# RBPZ_Dynamixel_TI.net
KiCad netlist of a schematic drawn in EAGLE
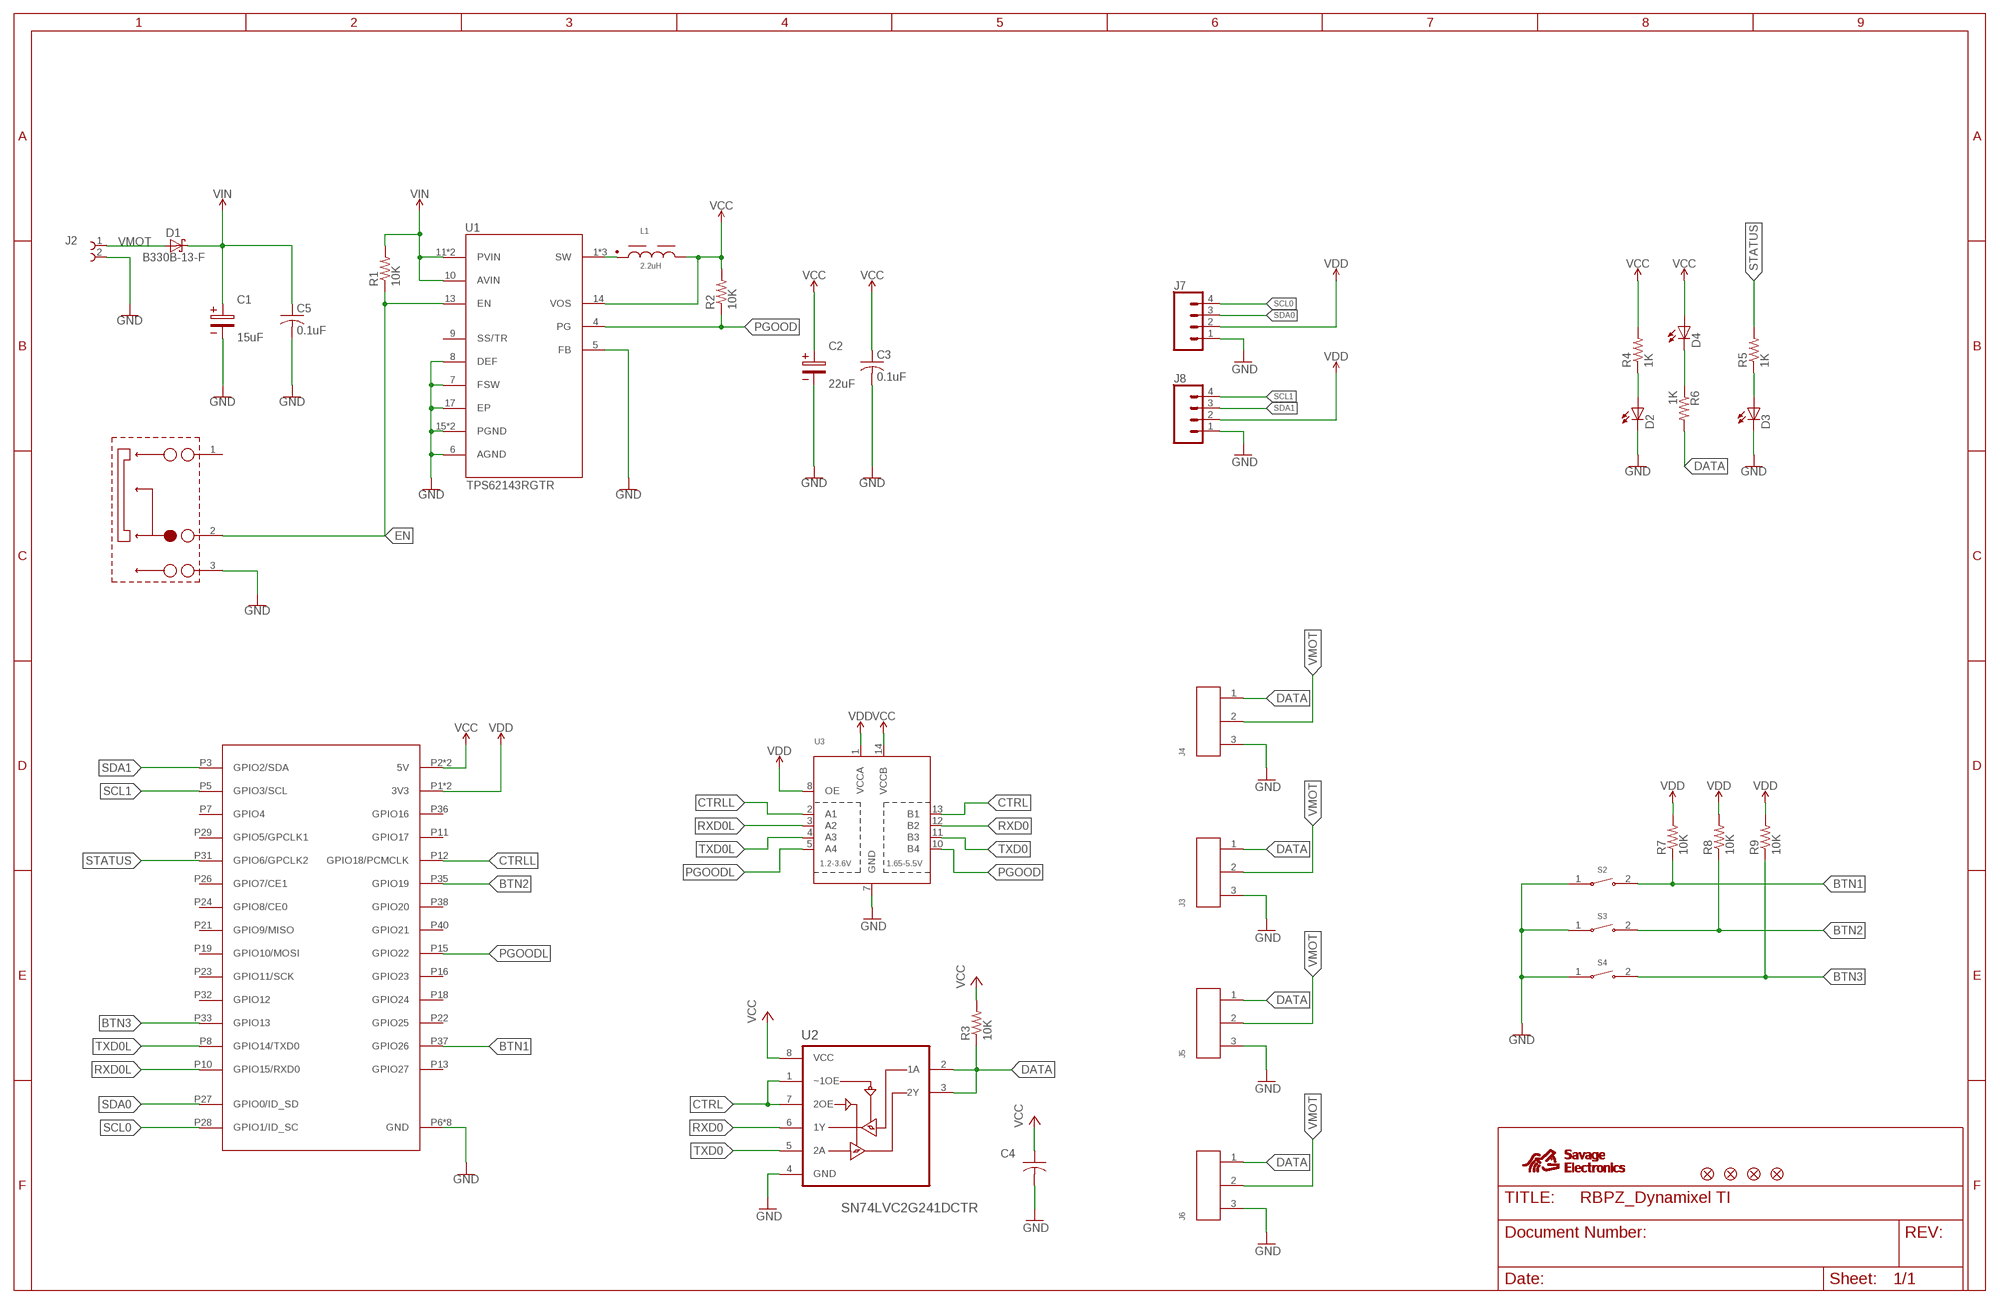
[diagram p0: schematic, sheet 1]

(export (version "E")
  (design (tool "Eeschema 10.0.6"))
  (components
    (comp (ref "C1")
      (value "15uF")
      (footprint "eagle-import:3.5X1.6X2.1(BXCXA)")
      (libsource (lib "eagle-import") (part "WCAP-ASLI_865080643007_6,3X5,5"))
    )
    (comp (ref "C2")
      (value "22uF")
      (footprint "eagle-import:3.5X1.6X2.1(BXCXA)")
      (libsource (lib "eagle-import") (part "WCAP-ASLI_865080643008_6,3X5,5"))
    )
    (comp (ref "C3")
      (value "0.1uF")
      (footprint "eagle-import:C0805")
      (libsource (lib "eagle-import") (part "C-USC0805"))
    )
    (comp (ref "C4")
      (value "1uF")
      (footprint "eagle-import:C0805")
      (libsource (lib "eagle-import") (part "C-USC0805"))
    )
    (comp (ref "C5")
      (value "0.1uF")
      (footprint "eagle-import:C0805")
      (libsource (lib "eagle-import") (part "C-USC0805"))
    )
    (comp (ref "D1")
      (value "B330B-13-F")
      (footprint "eagle-import:DIONM4336X250N")
      (libsource (lib "eagle-import") (part "B330B-13-F"))
    )
    (comp (ref "D2")
      (value "LEDCHIP-LED0805")
      (footprint "eagle-import:CHIP-LED0805")
      (libsource (lib "eagle-import") (part "LEDCHIP-LED0805"))
    )
    (comp (ref "D3")
      (value "LEDCHIP-LED0805")
      (footprint "eagle-import:CHIP-LED0805")
      (libsource (lib "eagle-import") (part "LEDCHIP-LED0805"))
    )
    (comp (ref "D4")
      (value "LEDCHIP-LED0805")
      (footprint "eagle-import:CHIP-LED0805")
      (libsource (lib "eagle-import") (part "LEDCHIP-LED0805"))
    )
    (comp (ref "FID1")
      (value "FIDUCIAL\"\"")
      (footprint "eagle-import:FIDUCIAL_1MM")
      (libsource (lib "eagle-import") (part "FIDUCIAL{dblquote}{dblquote}"))
    )
    (comp (ref "FID2")
      (value "FIDUCIAL\"\"")
      (footprint "eagle-import:FIDUCIAL_1MM")
      (libsource (lib "eagle-import") (part "FIDUCIAL{dblquote}{dblquote}"))
    )
    (comp (ref "FID3")
      (value "FIDUCIAL\"\"")
      (footprint "eagle-import:FIDUCIAL_1MM")
      (libsource (lib "eagle-import") (part "FIDUCIAL{dblquote}{dblquote}"))
    )
    (comp (ref "FID4")
      (value "FIDUCIAL\"\"")
      (footprint "eagle-import:FIDUCIAL_1MM")
      (libsource (lib "eagle-import") (part "FIDUCIAL{dblquote}{dblquote}"))
    )
    (comp (ref "J1")
      (value "RBPZERO")
      (footprint "eagle-import:61004021821_RASPBERRYPIZERO")
      (libsource (lib "eagle-import") (part "RBPZERO"))
    )
    (comp (ref "J2")
      (value "691137910002")
      (footprint "eagle-import:691137910002")
      (libsource (lib "eagle-import") (part "691137910002"))
    )
    (comp (ref "J3")
      (value "64600311622")
      (footprint "eagle-import:64600311622")
      (libsource (lib "eagle-import") (part "64600311622"))
    )
    (comp (ref "J4")
      (value "64600311622")
      (footprint "eagle-import:64600311622")
      (libsource (lib "eagle-import") (part "64600311622"))
    )
    (comp (ref "J5")
      (value "64600311622")
      (footprint "eagle-import:64600311622")
      (libsource (lib "eagle-import") (part "64600311622"))
    )
    (comp (ref "J6")
      (value "64600311622")
      (footprint "eagle-import:64600311622")
      (libsource (lib "eagle-import") (part "64600311622"))
    )
    (comp (ref "J7")
      (value "CONN_04SMD2")
      (footprint "eagle-import:1X04_1MM_RA")
      (libsource (lib "eagle-import") (part "CONN_04SMD2"))
    )
    (comp (ref "J8")
      (value "CONN_04SMD2")
      (footprint "eagle-import:1X04_1MM_RA")
      (libsource (lib "eagle-import") (part "CONN_04SMD2"))
    )
    (comp (ref "L1")
      (value "2.2uH")
      (footprint "eagle-import:WE-LQFS_48X8")
      (libsource (lib "eagle-import") (part "WE-LQFS_4818_74406042022"))
    )
    (comp (ref "R1")
      (value "10K")
      (footprint "eagle-import:R0805")
      (libsource (lib "eagle-import") (part "R-US_R0805"))
    )
    (comp (ref "R2")
      (value "10K")
      (footprint "eagle-import:R0805")
      (libsource (lib "eagle-import") (part "R-US_R0805"))
    )
    (comp (ref "R3")
      (value "10K")
      (footprint "eagle-import:R0805")
      (libsource (lib "eagle-import") (part "R-US_R0805"))
    )
    (comp (ref "R4")
      (value "1K")
      (footprint "eagle-import:R0805")
      (libsource (lib "eagle-import") (part "R-US_R0805"))
    )
    (comp (ref "R5")
      (value "1K")
      (footprint "eagle-import:R0805")
      (libsource (lib "eagle-import") (part "R-US_R0805"))
    )
    (comp (ref "R6")
      (value "1K")
      (footprint "eagle-import:R0805")
      (libsource (lib "eagle-import") (part "R-US_R0805"))
    )
    (comp (ref "R7")
      (value "10K")
      (footprint "eagle-import:R0805")
      (libsource (lib "eagle-import") (part "R-US_R0805"))
    )
    (comp (ref "R8")
      (value "10K")
      (footprint "eagle-import:R0805")
      (libsource (lib "eagle-import") (part "R-US_R0805"))
    )
    (comp (ref "R9")
      (value "10K")
      (footprint "eagle-import:R0805")
      (libsource (lib "eagle-import") (part "R-US_R0805"))
    )
    (comp (ref "S1")
      (value "450404015514")
      (footprint "eagle-import:450404015514")
      (libsource (lib "eagle-import") (part "450404015514"))
    )
    (comp (ref "S2")
      (value "434123025826-2PIN")
      (footprint "eagle-import:434123025826-2PIN")
      (libsource (lib "eagle-import") (part "434123025826-2PIN"))
    )
    (comp (ref "S3")
      (value "434123025826-2PIN")
      (footprint "eagle-import:434123025826-2PIN")
      (libsource (lib "eagle-import") (part "434123025826-2PIN"))
    )
    (comp (ref "S4")
      (value "434123025826-2PIN")
      (footprint "eagle-import:434123025826-2PIN")
      (libsource (lib "eagle-import") (part "434123025826-2PIN"))
    )
    (comp (ref "U1")
      (value "TPS62143RGTR")
      (footprint "eagle-import:QFN50P300X300X80-17N")
      (fields (field (name "MANUFACTURER") "Maxim Integrated"))
      (libsource (lib "eagle-import") (part "TPS62143"))
    )
    (comp (ref "U2")
      (value "SN74LVC2G241DCTR")
      (footprint "eagle-import:SOP65P400X130-8N")
      (fields (field (name "MF") "Texas Instruments") (field (name "MP") "SN74LVC2G241"))
      (libsource (lib "eagle-import") (part "SN74LVC2G241"))
    )
    (comp (ref "U3")
      (value "TXB0104PWR")
      (footprint "eagle-import:TSSOP14")
      (libsource (lib "eagle-import") (part "TXB0104PWR"))
    )
  )
  (nets
    (net (code "1") (name "BTN1") (class "Default")
      (node (ref "J1") (pin "P37") (pinfunction "GPIO26_P37") (pintype "bidirectional"))
      (node (ref "R7") (pin "1") (pinfunction "1_1") (pintype "passive"))
      (node (ref "S2") (pin "2") (pinfunction "2_2") (pintype "passive"))
    )
    (net (code "2") (name "BTN2") (class "Default")
      (node (ref "J1") (pin "P35") (pinfunction "GPIO19_P35") (pintype "bidirectional"))
      (node (ref "R8") (pin "1") (pinfunction "1_1") (pintype "passive"))
      (node (ref "S3") (pin "2") (pinfunction "2_2") (pintype "passive"))
    )
    (net (code "3") (name "BTN3") (class "Default")
      (node (ref "J1") (pin "P33") (pinfunction "GPIO13_P33") (pintype "bidirectional"))
      (node (ref "R9") (pin "1") (pinfunction "1_1") (pintype "passive"))
      (node (ref "S4") (pin "2") (pinfunction "2_2") (pintype "passive"))
    )
    (net (code "4") (name "CTRL") (class "Default")
      (node (ref "U2") (pin "1") (pinfunction "~{1OE}_1") (pintype "input"))
      (node (ref "U2") (pin "7") (pinfunction "2OE_7") (pintype "input"))
      (node (ref "U3") (pin "13") (pinfunction "B1_13") (pintype "bidirectional"))
    )
    (net (code "5") (name "CTRLL") (class "Default")
      (node (ref "J1") (pin "P12") (pinfunction "GPIO18/PCMCLK_P12") (pintype "bidirectional"))
      (node (ref "U3") (pin "2") (pinfunction "A1_2") (pintype "bidirectional"))
    )
    (net (code "6") (name "DATA") (class "Default")
      (node (ref "J3") (pin "1") (pinfunction "1_1") (pintype "passive"))
      (node (ref "J4") (pin "1") (pinfunction "1_1") (pintype "passive"))
      (node (ref "J5") (pin "1") (pinfunction "1_1") (pintype "passive"))
      (node (ref "J6") (pin "1") (pinfunction "1_1") (pintype "passive"))
      (node (ref "R3") (pin "1") (pinfunction "1_1") (pintype "passive"))
      (node (ref "R6") (pin "2") (pinfunction "2_2") (pintype "passive"))
      (node (ref "U2") (pin "2") (pinfunction "1A_2") (pintype "input"))
      (node (ref "U2") (pin "3") (pinfunction "2Y_3") (pintype "output"))
    )
    (net (code "7") (name "EN") (class "Default")
      (node (ref "R1") (pin "1") (pinfunction "1_1") (pintype "passive"))
      (node (ref "S1") (pin "2") (pinfunction "2_2") (pintype "passive"))
      (node (ref "U1") (pin "13") (pinfunction "EN_13") (pintype "bidirectional"))
    )
    (net (code "8") (name "GND") (class "Default")
      (node (ref "C1") (pin "2") (pinfunction "2_2") (pintype "passive"))
      (node (ref "C2") (pin "2") (pinfunction "2_2") (pintype "passive"))
      (node (ref "C3") (pin "2") (pinfunction "2_2") (pintype "passive"))
      (node (ref "C4") (pin "2") (pinfunction "2_2") (pintype "passive"))
      (node (ref "C5") (pin "2") (pinfunction "2_2") (pintype "passive"))
      (node (ref "D2") (pin "C") (pinfunction "C_C") (pintype "passive"))
      (node (ref "D3") (pin "C") (pinfunction "C_C") (pintype "passive"))
      (node (ref "J1") (pin "P14") (pinfunction "GND_P14") (pintype "bidirectional"))
      (node (ref "J1") (pin "P20") (pinfunction "GND_P20") (pintype "bidirectional"))
      (node (ref "J1") (pin "P25") (pinfunction "GND_P25") (pintype "bidirectional"))
      (node (ref "J1") (pin "P30") (pinfunction "GND_P30") (pintype "bidirectional"))
      (node (ref "J1") (pin "P34") (pinfunction "GND_P34") (pintype "bidirectional"))
      (node (ref "J1") (pin "P39") (pinfunction "GND_P39") (pintype "bidirectional"))
      (node (ref "J1") (pin "P6") (pinfunction "GND_P6") (pintype "bidirectional"))
      (node (ref "J1") (pin "P9") (pinfunction "GND_P9") (pintype "bidirectional"))
      (node (ref "J2") (pin "2") (pinfunction "2_2") (pintype "passive"))
      (node (ref "J3") (pin "3") (pinfunction "3_3") (pintype "passive"))
      (node (ref "J4") (pin "3") (pinfunction "3_3") (pintype "passive"))
      (node (ref "J5") (pin "3") (pinfunction "3_3") (pintype "passive"))
      (node (ref "J6") (pin "3") (pinfunction "3_3") (pintype "passive"))
      (node (ref "J7") (pin "1") (pinfunction "1_1") (pintype "passive"))
      (node (ref "J8") (pin "1") (pinfunction "1_1") (pintype "passive"))
      (node (ref "S1") (pin "3") (pinfunction "3_3") (pintype "passive"))
      (node (ref "S2") (pin "1") (pinfunction "1_1") (pintype "passive"))
      (node (ref "S3") (pin "1") (pinfunction "1_1") (pintype "passive"))
      (node (ref "S4") (pin "1") (pinfunction "1_1") (pintype "passive"))
      (node (ref "U1") (pin "15") (pinfunction "PGND_15") (pintype "bidirectional"))
      (node (ref "U1") (pin "16") (pinfunction "PGND_16") (pintype "bidirectional"))
      (node (ref "U1") (pin "17") (pinfunction "EP_17") (pintype "bidirectional"))
      (node (ref "U1") (pin "5") (pinfunction "FB_5") (pintype "bidirectional"))
      (node (ref "U1") (pin "6") (pinfunction "AGND_6") (pintype "bidirectional"))
      (node (ref "U1") (pin "7") (pinfunction "FSW_7") (pintype "bidirectional"))
      (node (ref "U1") (pin "8") (pinfunction "DEF_8") (pintype "bidirectional"))
      (node (ref "U2") (pin "4") (pinfunction "GND_4") (pintype "passive"))
      (node (ref "U3") (pin "7") (pinfunction "GND_7") (pintype "bidirectional"))
    )
    (net (code "9") (name "Net-(D2-PadA)") (class "Default")
      (node (ref "D2") (pin "A") (pinfunction "A_A") (pintype "passive"))
      (node (ref "R4") (pin "1") (pinfunction "1_1") (pintype "passive"))
    )
    (net (code "10") (name "Net-(D3-PadA)") (class "Default")
      (node (ref "D3") (pin "A") (pinfunction "A_A") (pintype "passive"))
      (node (ref "R5") (pin "1") (pinfunction "1_1") (pintype "passive"))
    )
    (net (code "11") (name "Net-(D4-PadC)") (class "Default")
      (node (ref "D4") (pin "C") (pinfunction "C_C") (pintype "passive"))
      (node (ref "R6") (pin "1") (pinfunction "1_1") (pintype "passive"))
    )
    (net (code "12") (name "Net-(L1-Pad1)") (class "Default")
      (node (ref "L1") (pin "1") (pinfunction "1_1") (pintype "passive"))
      (node (ref "U1") (pin "1") (pinfunction "SW_1") (pintype "bidirectional"))
      (node (ref "U1") (pin "2") (pinfunction "SW_2") (pintype "bidirectional"))
      (node (ref "U1") (pin "3") (pinfunction "SW_3") (pintype "bidirectional"))
    )
    (net (code "13") (name "PGOOD") (class "Default")
      (node (ref "R2") (pin "1") (pinfunction "1_1") (pintype "passive"))
      (node (ref "U1") (pin "4") (pinfunction "PG_4") (pintype "bidirectional"))
      (node (ref "U3") (pin "10") (pinfunction "B4_10") (pintype "bidirectional"))
    )
    (net (code "14") (name "PGOODL") (class "Default")
      (node (ref "J1") (pin "P15") (pinfunction "GPIO22_P15") (pintype "bidirectional"))
      (node (ref "U3") (pin "5") (pinfunction "A4_5") (pintype "bidirectional"))
    )
    (net (code "15") (name "RXD0") (class "Default")
      (node (ref "U2") (pin "6") (pinfunction "1Y_6") (pintype "output"))
      (node (ref "U3") (pin "12") (pinfunction "B2_12") (pintype "bidirectional"))
    )
    (net (code "16") (name "RXD0L") (class "Default")
      (node (ref "J1") (pin "P10") (pinfunction "GPIO15/RXD0_P10") (pintype "bidirectional"))
      (node (ref "U3") (pin "3") (pinfunction "A2_3") (pintype "bidirectional"))
    )
    (net (code "17") (name "SCL0") (class "Default")
      (node (ref "J1") (pin "P28") (pinfunction "GPIO1/ID_SC_P28") (pintype "bidirectional"))
      (node (ref "J7") (pin "4") (pinfunction "4_4") (pintype "passive"))
    )
    (net (code "18") (name "SCL1") (class "Default")
      (node (ref "J1") (pin "P5") (pinfunction "GPIO3/SCL_P5") (pintype "bidirectional"))
      (node (ref "J8") (pin "4") (pinfunction "4_4") (pintype "passive"))
    )
    (net (code "19") (name "SDA0") (class "Default")
      (node (ref "J1") (pin "P27") (pinfunction "GPIO0/ID_SD_P27") (pintype "bidirectional"))
      (node (ref "J7") (pin "3") (pinfunction "3_3") (pintype "passive"))
    )
    (net (code "20") (name "SDA1") (class "Default")
      (node (ref "J1") (pin "P3") (pinfunction "GPIO2/SDA_P3") (pintype "bidirectional"))
      (node (ref "J8") (pin "3") (pinfunction "3_3") (pintype "passive"))
    )
    (net (code "21") (name "STATUS") (class "Default")
      (node (ref "J1") (pin "P31") (pinfunction "GPIO6/GPCLK2_P31") (pintype "bidirectional"))
      (node (ref "R5") (pin "2") (pinfunction "2_2") (pintype "passive"))
    )
    (net (code "22") (name "TXD0") (class "Default")
      (node (ref "U2") (pin "5") (pinfunction "2A_5") (pintype "input"))
      (node (ref "U3") (pin "11") (pinfunction "B3_11") (pintype "bidirectional"))
    )
    (net (code "23") (name "TXD0L") (class "Default")
      (node (ref "J1") (pin "P8") (pinfunction "GPIO14/TXD0_P8") (pintype "bidirectional"))
      (node (ref "U3") (pin "4") (pinfunction "A3_4") (pintype "bidirectional"))
    )
    (net (code "24") (name "VCC") (class "Default")
      (node (ref "C2") (pin "1") (pinfunction "1_1") (pintype "passive"))
      (node (ref "C3") (pin "1") (pinfunction "1_1") (pintype "passive"))
      (node (ref "C4") (pin "1") (pinfunction "1_1") (pintype "passive"))
      (node (ref "D4") (pin "A") (pinfunction "A_A") (pintype "passive"))
      (node (ref "J1") (pin "P2") (pinfunction "5V_P2") (pintype "bidirectional"))
      (node (ref "J1") (pin "P4") (pinfunction "5V_P4") (pintype "bidirectional"))
      (node (ref "L1") (pin "2") (pinfunction "2_2") (pintype "passive"))
      (node (ref "R2") (pin "2") (pinfunction "2_2") (pintype "passive"))
      (node (ref "R3") (pin "2") (pinfunction "2_2") (pintype "passive"))
      (node (ref "R4") (pin "2") (pinfunction "2_2") (pintype "passive"))
      (node (ref "U1") (pin "14") (pinfunction "VOS_14") (pintype "bidirectional"))
      (node (ref "U2") (pin "8") (pinfunction "VCC_8") (pintype "power_in"))
      (node (ref "U3") (pin "14") (pinfunction "VCCB_14") (pintype "bidirectional"))
    )
    (net (code "25") (name "VDD") (class "Default")
      (node (ref "J1") (pin "P1") (pinfunction "3V3_P1") (pintype "bidirectional"))
      (node (ref "J1") (pin "P17") (pinfunction "3V3_P17") (pintype "bidirectional"))
      (node (ref "J7") (pin "2") (pinfunction "2_2") (pintype "passive"))
      (node (ref "J8") (pin "2") (pinfunction "2_2") (pintype "passive"))
      (node (ref "R7") (pin "2") (pinfunction "2_2") (pintype "passive"))
      (node (ref "R8") (pin "2") (pinfunction "2_2") (pintype "passive"))
      (node (ref "R9") (pin "2") (pinfunction "2_2") (pintype "passive"))
      (node (ref "U3") (pin "1") (pinfunction "VCCA_1") (pintype "bidirectional"))
      (node (ref "U3") (pin "8") (pinfunction "OE_8") (pintype "bidirectional"))
    )
    (net (code "26") (name "VIN") (class "Default")
      (node (ref "C1") (pin "1") (pinfunction "1_1") (pintype "passive"))
      (node (ref "C5") (pin "1") (pinfunction "1_1") (pintype "passive"))
      (node (ref "D1") (pin "1") (pinfunction "C_1") (pintype "passive"))
      (node (ref "R1") (pin "2") (pinfunction "2_2") (pintype "passive"))
      (node (ref "U1") (pin "10") (pinfunction "AVIN_10") (pintype "bidirectional"))
      (node (ref "U1") (pin "11") (pinfunction "PVIN_11") (pintype "bidirectional"))
      (node (ref "U1") (pin "12") (pinfunction "PVIN_12") (pintype "bidirectional"))
    )
    (net (code "27") (name "VMOT") (class "Default")
      (node (ref "D1") (pin "2") (pinfunction "A_2") (pintype "passive"))
      (node (ref "J2") (pin "1") (pinfunction "1_1") (pintype "passive"))
      (node (ref "J3") (pin "2") (pinfunction "2_2") (pintype "passive"))
      (node (ref "J4") (pin "2") (pinfunction "2_2") (pintype "passive"))
      (node (ref "J5") (pin "2") (pinfunction "2_2") (pintype "passive"))
      (node (ref "J6") (pin "2") (pinfunction "2_2") (pintype "passive"))
    )
    (net (code "28") (name "unconnected-(J1-GPIO4-PadP7)") (class "Default")
      (node (ref "J1") (pin "P7") (pinfunction "GPIO4_P7") (pintype "bidirectional"))
    )
    (net (code "29") (name "unconnected-(J1-GPIO5{slash}GPCLK1-PadP29)") (class "Default")
      (node (ref "J1") (pin "P29") (pinfunction "GPIO5/GPCLK1_P29") (pintype "bidirectional"))
    )
    (net (code "30") (name "unconnected-(J1-GPIO7{slash}CE1-PadP26)") (class "Default")
      (node (ref "J1") (pin "P26") (pinfunction "GPIO7/CE1_P26") (pintype "bidirectional"))
    )
    (net (code "31") (name "unconnected-(J1-GPIO8{slash}CE0-PadP24)") (class "Default")
      (node (ref "J1") (pin "P24") (pinfunction "GPIO8/CE0_P24") (pintype "bidirectional"))
    )
    (net (code "32") (name "unconnected-(J1-GPIO9{slash}MISO-PadP21)") (class "Default")
      (node (ref "J1") (pin "P21") (pinfunction "GPIO9/MISO_P21") (pintype "bidirectional"))
    )
    (net (code "33") (name "unconnected-(J1-GPIO10{slash}MOSI-PadP19)") (class "Default")
      (node (ref "J1") (pin "P19") (pinfunction "GPIO10/MOSI_P19") (pintype "bidirectional"))
    )
    (net (code "34") (name "unconnected-(J1-GPIO11{slash}SCK-PadP23)") (class "Default")
      (node (ref "J1") (pin "P23") (pinfunction "GPIO11/SCK_P23") (pintype "bidirectional"))
    )
    (net (code "35") (name "unconnected-(J1-GPIO12-PadP32)") (class "Default")
      (node (ref "J1") (pin "P32") (pinfunction "GPIO12_P32") (pintype "bidirectional"))
    )
    (net (code "36") (name "unconnected-(J1-GPIO16-PadP36)") (class "Default")
      (node (ref "J1") (pin "P36") (pinfunction "GPIO16_P36") (pintype "bidirectional"))
    )
    (net (code "37") (name "unconnected-(J1-GPIO17-PadP11)") (class "Default")
      (node (ref "J1") (pin "P11") (pinfunction "GPIO17_P11") (pintype "bidirectional"))
    )
    (net (code "38") (name "unconnected-(J1-GPIO20-PadP38)") (class "Default")
      (node (ref "J1") (pin "P38") (pinfunction "GPIO20_P38") (pintype "bidirectional"))
    )
    (net (code "39") (name "unconnected-(J1-GPIO21-PadP40)") (class "Default")
      (node (ref "J1") (pin "P40") (pinfunction "GPIO21_P40") (pintype "bidirectional"))
    )
    (net (code "40") (name "unconnected-(J1-GPIO23-PadP16)") (class "Default")
      (node (ref "J1") (pin "P16") (pinfunction "GPIO23_P16") (pintype "bidirectional"))
    )
    (net (code "41") (name "unconnected-(J1-GPIO24-PadP18)") (class "Default")
      (node (ref "J1") (pin "P18") (pinfunction "GPIO24_P18") (pintype "bidirectional"))
    )
    (net (code "42") (name "unconnected-(J1-GPIO25-PadP22)") (class "Default")
      (node (ref "J1") (pin "P22") (pinfunction "GPIO25_P22") (pintype "bidirectional"))
    )
    (net (code "43") (name "unconnected-(J1-GPIO27-PadP13)") (class "Default")
      (node (ref "J1") (pin "P13") (pinfunction "GPIO27_P13") (pintype "bidirectional"))
    )
    (net (code "44") (name "unconnected-(S1-Pad1)") (class "Default")
      (node (ref "S1") (pin "1") (pinfunction "1_1") (pintype "passive"))
    )
    (net (code "45") (name "unconnected-(U1-SS{slash}TR-Pad9)") (class "Default")
      (node (ref "U1") (pin "9") (pinfunction "SS/TR_9") (pintype "bidirectional"))
    )
  )
)
